# hw_interface_board.net
KiCad netlist of a schematic drawn in EAGLE
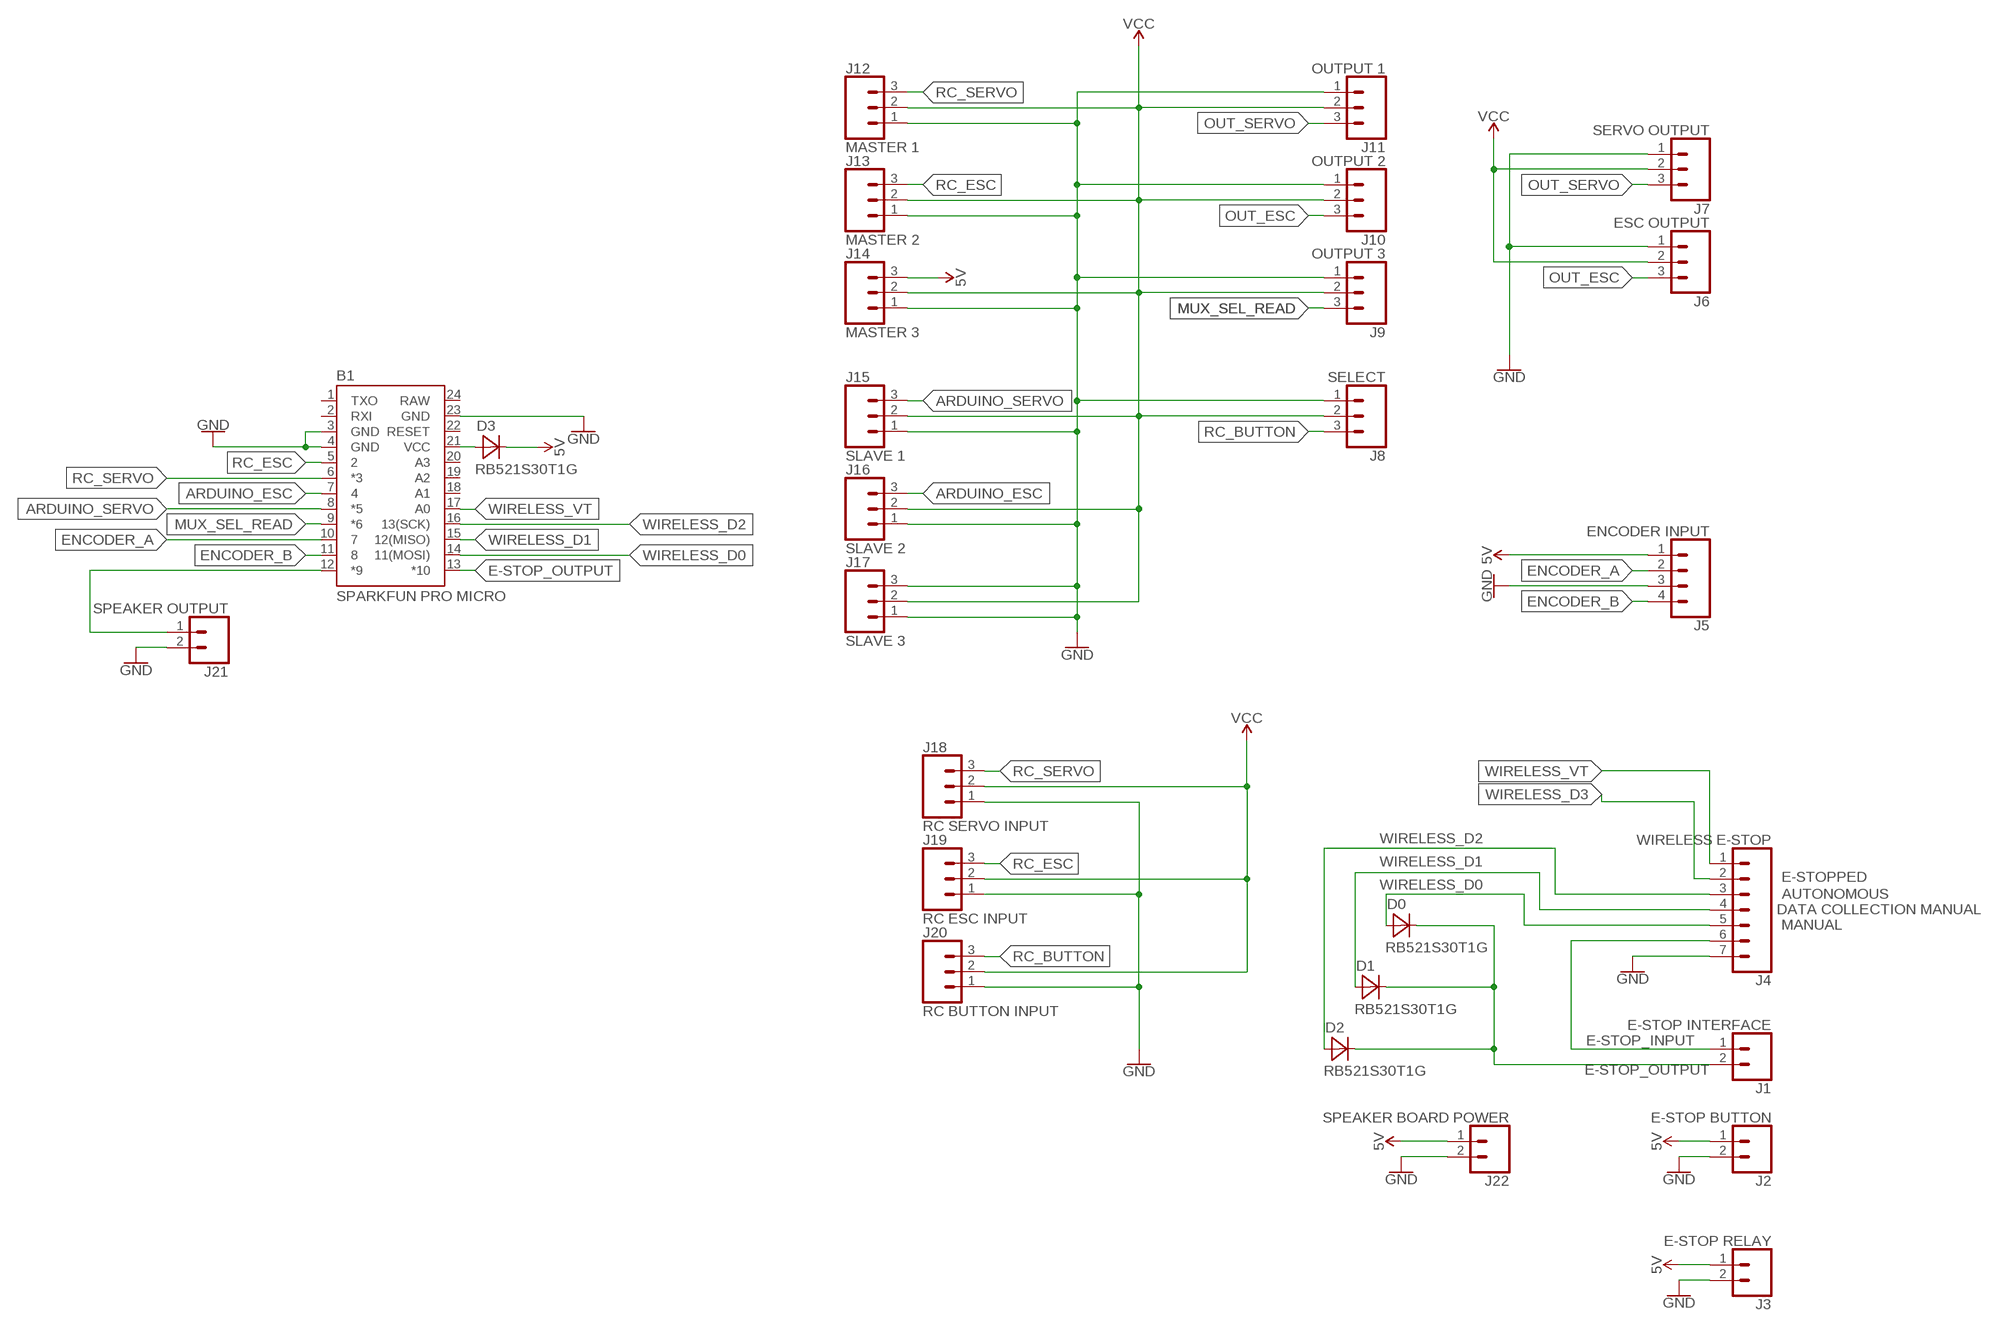
[diagram p0: schematic, sheet 1]

(export (version "E")
  (design (tool "Eeschema 10.0.6"))
  (components
    (comp (ref "B1")
      (value "SPARKFUN PRO MICRO")
      (footprint "eagle-import:SPARKFUN_PRO_MICRO")
      (libsource (lib "eagle-import") (part "SPARKFUN_PRO_MICRO"))
    )
    (comp (ref "D0")
      (value "RB521S30T1G")
      (footprint "eagle-import:SOD523")
      (libsource (lib "eagle-import") (part "RB521S30T1G"))
    )
    (comp (ref "D1")
      (value "RB521S30T1G")
      (footprint "eagle-import:SOD523")
      (libsource (lib "eagle-import") (part "RB521S30T1G"))
    )
    (comp (ref "D2")
      (value "RB521S30T1G")
      (footprint "eagle-import:SOD523")
      (libsource (lib "eagle-import") (part "RB521S30T1G"))
    )
    (comp (ref "D3")
      (value "RB521S30T1G")
      (footprint "eagle-import:SOD523")
      (libsource (lib "eagle-import") (part "RB521S30T1G"))
    )
    (comp (ref "J1")
      (value "E-STOP INTERFACE")
      (footprint "eagle-import:1X02")
      (libsource (lib "eagle-import") (part "CONN_02"))
    )
    (comp (ref "J2")
      (value "E-STOP BUTTON")
      (footprint "eagle-import:1X02")
      (libsource (lib "eagle-import") (part "CONN_02"))
    )
    (comp (ref "J3")
      (value "E-STOP RELAY")
      (footprint "eagle-import:1X02")
      (libsource (lib "eagle-import") (part "CONN_02"))
    )
    (comp (ref "J4")
      (value "WIRELESS E-STOP")
      (footprint "eagle-import:1X07")
      (libsource (lib "eagle-import") (part "CONN_07"))
    )
    (comp (ref "J5")
      (value "ENCODER INPUT")
      (footprint "eagle-import:1X04")
      (libsource (lib "eagle-import") (part "CONN_04"))
    )
    (comp (ref "J6")
      (value "ESC OUTPUT")
      (footprint "eagle-import:1X03")
      (libsource (lib "eagle-import") (part "CONN_03"))
    )
    (comp (ref "J7")
      (value "SERVO OUTPUT")
      (footprint "eagle-import:1X03")
      (libsource (lib "eagle-import") (part "CONN_03"))
    )
    (comp (ref "J8")
      (value "SELECT")
      (footprint "eagle-import:1X03")
      (libsource (lib "eagle-import") (part "CONN_03"))
    )
    (comp (ref "J9")
      (value "OUTPUT 3")
      (footprint "eagle-import:1X03")
      (libsource (lib "eagle-import") (part "CONN_03"))
    )
    (comp (ref "J10")
      (value "OUTPUT 2")
      (footprint "eagle-import:1X03")
      (libsource (lib "eagle-import") (part "CONN_03"))
    )
    (comp (ref "J11")
      (value "OUTPUT 1")
      (footprint "eagle-import:1X03")
      (libsource (lib "eagle-import") (part "CONN_03"))
    )
    (comp (ref "J12")
      (value "MASTER 1")
      (footprint "eagle-import:1X03")
      (libsource (lib "eagle-import") (part "CONN_03"))
    )
    (comp (ref "J13")
      (value "MASTER 2")
      (footprint "eagle-import:1X03")
      (libsource (lib "eagle-import") (part "CONN_03"))
    )
    (comp (ref "J14")
      (value "MASTER 3")
      (footprint "eagle-import:1X03")
      (libsource (lib "eagle-import") (part "CONN_03"))
    )
    (comp (ref "J15")
      (value "SLAVE 1")
      (footprint "eagle-import:1X03")
      (libsource (lib "eagle-import") (part "CONN_03"))
    )
    (comp (ref "J16")
      (value "SLAVE 2")
      (footprint "eagle-import:1X03")
      (libsource (lib "eagle-import") (part "CONN_03"))
    )
    (comp (ref "J17")
      (value "SLAVE 3")
      (footprint "eagle-import:1X03")
      (libsource (lib "eagle-import") (part "CONN_03"))
    )
    (comp (ref "J18")
      (value "RC SERVO INPUT")
      (footprint "eagle-import:1X03")
      (libsource (lib "eagle-import") (part "CONN_03"))
    )
    (comp (ref "J19")
      (value "RC ESC INPUT")
      (footprint "eagle-import:1X03")
      (libsource (lib "eagle-import") (part "CONN_03"))
    )
    (comp (ref "J20")
      (value "RC BUTTON INPUT")
      (footprint "eagle-import:1X03")
      (libsource (lib "eagle-import") (part "CONN_03"))
    )
    (comp (ref "J21")
      (value "SPEAKER OUTPUT")
      (footprint "eagle-import:1X02")
      (libsource (lib "eagle-import") (part "CONN_02"))
    )
    (comp (ref "J22")
      (value "SPEAKER BOARD POWER")
      (footprint "eagle-import:1X02")
      (libsource (lib "eagle-import") (part "CONN_02"))
    )
  )
  (nets
    (net (code "1") (name "/E-STOP_INPUT") (class "Default")
      (node (ref "J1") (pin "1") (pinfunction "1_1") (pintype "passive"))
      (node (ref "J4") (pin "6") (pinfunction "6_6") (pintype "passive"))
    )
    (net (code "2") (name "/RAW") (class "Default")
      (node (ref "B1") (pin "24") (pinfunction "RAW_24") (pintype "power_in"))
    )
    (net (code "3") (name "5V") (class "Default")
      (node (ref "D3") (pin "C") (pinfunction "C_C") (pintype "passive"))
      (node (ref "J14") (pin "3") (pinfunction "3_3") (pintype "passive"))
      (node (ref "J2") (pin "1") (pinfunction "1_1") (pintype "passive"))
      (node (ref "J22") (pin "1") (pinfunction "1_1") (pintype "passive"))
      (node (ref "J3") (pin "1") (pinfunction "1_1") (pintype "passive"))
      (node (ref "J5") (pin "1") (pinfunction "1_1") (pintype "passive"))
    )
    (net (code "4") (name "ARDUINO_ESC") (class "Default")
      (node (ref "B1") (pin "7") (pinfunction "4_7") (pintype "bidirectional"))
      (node (ref "J16") (pin "3") (pinfunction "3_3") (pintype "passive"))
    )
    (net (code "5") (name "ARDUINO_SERVO") (class "Default")
      (node (ref "B1") (pin "8") (pinfunction "*5_8") (pintype "bidirectional"))
      (node (ref "J15") (pin "3") (pinfunction "3_3") (pintype "passive"))
    )
    (net (code "6") (name "E-STOP_OUTPUT") (class "Default")
      (node (ref "B1") (pin "13") (pinfunction "*10_13") (pintype "bidirectional"))
      (node (ref "D0") (pin "C") (pinfunction "C_C") (pintype "passive"))
      (node (ref "D1") (pin "C") (pinfunction "C_C") (pintype "passive"))
      (node (ref "D2") (pin "C") (pinfunction "C_C") (pintype "passive"))
      (node (ref "J1") (pin "2") (pinfunction "2_2") (pintype "passive"))
    )
    (net (code "7") (name "ENCODER_A") (class "Default")
      (node (ref "B1") (pin "10") (pinfunction "7_10") (pintype "bidirectional"))
      (node (ref "J5") (pin "2") (pinfunction "2_2") (pintype "passive"))
    )
    (net (code "8") (name "ENCODER_B") (class "Default")
      (node (ref "B1") (pin "11") (pinfunction "8_11") (pintype "bidirectional"))
      (node (ref "J5") (pin "4") (pinfunction "4_4") (pintype "passive"))
    )
    (net (code "9") (name "GND") (class "Default")
      (node (ref "B1") (pin "23") (pinfunction "GND_23") (pintype "power_in"))
      (node (ref "B1") (pin "3") (pinfunction "GND_3") (pintype "power_in"))
      (node (ref "B1") (pin "4") (pinfunction "GND_4") (pintype "power_in"))
      (node (ref "J10") (pin "1") (pinfunction "1_1") (pintype "passive"))
      (node (ref "J11") (pin "1") (pinfunction "1_1") (pintype "passive"))
      (node (ref "J12") (pin "1") (pinfunction "1_1") (pintype "passive"))
      (node (ref "J13") (pin "1") (pinfunction "1_1") (pintype "passive"))
      (node (ref "J14") (pin "1") (pinfunction "1_1") (pintype "passive"))
      (node (ref "J15") (pin "1") (pinfunction "1_1") (pintype "passive"))
      (node (ref "J16") (pin "1") (pinfunction "1_1") (pintype "passive"))
      (node (ref "J17") (pin "1") (pinfunction "1_1") (pintype "passive"))
      (node (ref "J17") (pin "3") (pinfunction "3_3") (pintype "passive"))
      (node (ref "J18") (pin "1") (pinfunction "1_1") (pintype "passive"))
      (node (ref "J19") (pin "1") (pinfunction "1_1") (pintype "passive"))
      (node (ref "J2") (pin "2") (pinfunction "2_2") (pintype "passive"))
      (node (ref "J20") (pin "1") (pinfunction "1_1") (pintype "passive"))
      (node (ref "J21") (pin "2") (pinfunction "2_2") (pintype "passive"))
      (node (ref "J22") (pin "2") (pinfunction "2_2") (pintype "passive"))
      (node (ref "J3") (pin "2") (pinfunction "2_2") (pintype "passive"))
      (node (ref "J4") (pin "7") (pinfunction "7_7") (pintype "passive"))
      (node (ref "J5") (pin "3") (pinfunction "3_3") (pintype "passive"))
      (node (ref "J6") (pin "1") (pinfunction "1_1") (pintype "passive"))
      (node (ref "J7") (pin "1") (pinfunction "1_1") (pintype "passive"))
      (node (ref "J8") (pin "1") (pinfunction "1_1") (pintype "passive"))
      (node (ref "J9") (pin "1") (pinfunction "1_1") (pintype "passive"))
    )
    (net (code "10") (name "MUX_SEL_READ") (class "Default")
      (node (ref "B1") (pin "9") (pinfunction "*6_9") (pintype "bidirectional"))
      (node (ref "J9") (pin "3") (pinfunction "3_3") (pintype "passive"))
    )
    (net (code "11") (name "Net-(B1-*9)") (class "Default")
      (node (ref "B1") (pin "12") (pinfunction "*9_12") (pintype "bidirectional"))
      (node (ref "J21") (pin "1") (pinfunction "1_1") (pintype "passive"))
    )
    (net (code "12") (name "Net-(B1-VCC)") (class "Default")
      (node (ref "B1") (pin "21") (pinfunction "VCC_21") (pintype "power_in"))
      (node (ref "D3") (pin "A") (pinfunction "A_A") (pintype "passive"))
    )
    (net (code "13") (name "OUT_ESC") (class "Default")
      (node (ref "J10") (pin "3") (pinfunction "3_3") (pintype "passive"))
      (node (ref "J6") (pin "3") (pinfunction "3_3") (pintype "passive"))
    )
    (net (code "14") (name "OUT_SERVO") (class "Default")
      (node (ref "J11") (pin "3") (pinfunction "3_3") (pintype "passive"))
      (node (ref "J7") (pin "3") (pinfunction "3_3") (pintype "passive"))
    )
    (net (code "15") (name "RC_BUTTON") (class "Default")
      (node (ref "J20") (pin "3") (pinfunction "3_3") (pintype "passive"))
      (node (ref "J8") (pin "3") (pinfunction "3_3") (pintype "passive"))
    )
    (net (code "16") (name "RC_ESC") (class "Default")
      (node (ref "B1") (pin "5") (pinfunction "2_5") (pintype "bidirectional"))
      (node (ref "J13") (pin "3") (pinfunction "3_3") (pintype "passive"))
      (node (ref "J19") (pin "3") (pinfunction "3_3") (pintype "passive"))
    )
    (net (code "17") (name "RC_SERVO") (class "Default")
      (node (ref "B1") (pin "6") (pinfunction "*3_6") (pintype "bidirectional"))
      (node (ref "J12") (pin "3") (pinfunction "3_3") (pintype "passive"))
      (node (ref "J18") (pin "3") (pinfunction "3_3") (pintype "passive"))
    )
    (net (code "18") (name "VCC") (class "Default")
      (node (ref "J10") (pin "2") (pinfunction "2_2") (pintype "passive"))
      (node (ref "J11") (pin "2") (pinfunction "2_2") (pintype "passive"))
      (node (ref "J12") (pin "2") (pinfunction "2_2") (pintype "passive"))
      (node (ref "J13") (pin "2") (pinfunction "2_2") (pintype "passive"))
      (node (ref "J14") (pin "2") (pinfunction "2_2") (pintype "passive"))
      (node (ref "J15") (pin "2") (pinfunction "2_2") (pintype "passive"))
      (node (ref "J16") (pin "2") (pinfunction "2_2") (pintype "passive"))
      (node (ref "J17") (pin "2") (pinfunction "2_2") (pintype "passive"))
      (node (ref "J18") (pin "2") (pinfunction "2_2") (pintype "passive"))
      (node (ref "J19") (pin "2") (pinfunction "2_2") (pintype "passive"))
      (node (ref "J20") (pin "2") (pinfunction "2_2") (pintype "passive"))
      (node (ref "J6") (pin "2") (pinfunction "2_2") (pintype "passive"))
      (node (ref "J7") (pin "2") (pinfunction "2_2") (pintype "passive"))
      (node (ref "J8") (pin "2") (pinfunction "2_2") (pintype "passive"))
      (node (ref "J9") (pin "2") (pinfunction "2_2") (pintype "passive"))
    )
    (net (code "19") (name "WIRELESS_D0") (class "Default")
      (node (ref "B1") (pin "14") (pinfunction "11(MOSI)_14") (pintype "bidirectional"))
      (node (ref "D0") (pin "A") (pinfunction "A_A") (pintype "passive"))
      (node (ref "J4") (pin "5") (pinfunction "5_5") (pintype "passive"))
    )
    (net (code "20") (name "WIRELESS_D1") (class "Default")
      (node (ref "B1") (pin "15") (pinfunction "12(MISO)_15") (pintype "bidirectional"))
      (node (ref "D1") (pin "A") (pinfunction "A_A") (pintype "passive"))
      (node (ref "J4") (pin "4") (pinfunction "4_4") (pintype "passive"))
    )
    (net (code "21") (name "WIRELESS_D2") (class "Default")
      (node (ref "B1") (pin "16") (pinfunction "13(SCK)_16") (pintype "bidirectional"))
      (node (ref "D2") (pin "A") (pinfunction "A_A") (pintype "passive"))
      (node (ref "J4") (pin "3") (pinfunction "3_3") (pintype "passive"))
    )
    (net (code "22") (name "WIRELESS_D3") (class "Default")
      (node (ref "J4") (pin "2") (pinfunction "2_2") (pintype "passive"))
    )
    (net (code "23") (name "WIRELESS_VT") (class "Default")
      (node (ref "B1") (pin "17") (pinfunction "A0_17") (pintype "bidirectional"))
      (node (ref "J4") (pin "1") (pinfunction "1_1") (pintype "passive"))
    )
    (net (code "24") (name "unconnected-(B1-A1-Pad18)") (class "Default")
      (node (ref "B1") (pin "18") (pinfunction "A1_18") (pintype "bidirectional"))
    )
    (net (code "25") (name "unconnected-(B1-A2-Pad19)") (class "Default")
      (node (ref "B1") (pin "19") (pinfunction "A2_19") (pintype "bidirectional"))
    )
    (net (code "26") (name "unconnected-(B1-A3-Pad20)") (class "Default")
      (node (ref "B1") (pin "20") (pinfunction "A3_20") (pintype "bidirectional"))
    )
    (net (code "27") (name "unconnected-(B1-RESET-Pad22)") (class "Default")
      (node (ref "B1") (pin "22") (pinfunction "RESET_22") (pintype "bidirectional"))
    )
    (net (code "28") (name "unconnected-(B1-RXI-Pad2)") (class "Default")
      (node (ref "B1") (pin "2") (pinfunction "RXI_2") (pintype "bidirectional"))
    )
    (net (code "29") (name "unconnected-(B1-TXO-Pad1)") (class "Default")
      (node (ref "B1") (pin "1") (pinfunction "TXO_1") (pintype "bidirectional"))
    )
  )
)
